# P_EV.net
KiCad netlist of a schematic drawn in Altium Designer
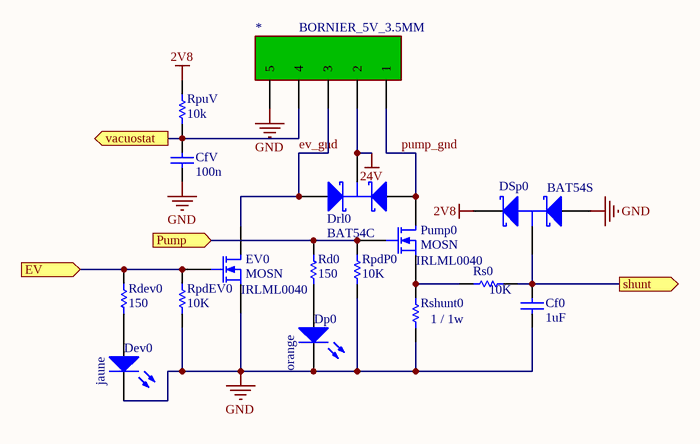
[diagram p0: P+EV.SchDoc]

(export (version "E")
  (design (tool "Eeschema 10.0.6"))
  (components
    (comp (ref "*")
      (value "BORNIER_5V_3.5MM")
      (footprint "BORNIER_5V_3.5MM_femelle_90")
      (libsource (lib "Connecteur") (part "BORNIER_5V_3.5MM"))
    )
    (comp (ref "Cf0")
      (value "1uF")
      (footprint "C0805_N")
      (description "Capacitor")
      (fields (field (name "PUBLISHER") "Altium Limited"))
      (libsource (lib "_ROBOT") (part "Condensateur"))
    )
    (comp (ref "CfV")
      (value "100n")
      (footprint "C0805_N")
      (description "Capacitor")
      (fields (field (name "PUBLISHER") "Altium Limited"))
      (libsource (lib "_ROBOT") (part "Condensateur"))
    )
    (comp (ref "Dev0")
      (value "jaune")
      (footprint "LED_0805")
      (description "Typical LED")
      (fields (field (name "PUBLISHER") "Altium Limited"))
      (libsource (lib "_ROBOT") (part "LED"))
    )
    (comp (ref "Dp0")
      (value "orange")
      (footprint "LED_0805")
      (description "Typical LED")
      (fields (field (name "PUBLISHER") "Altium Limited"))
      (libsource (lib "_ROBOT") (part "LED"))
    )
    (comp (ref "Drl0")
      (value "BAT54C")
      (footprint "SOT23-3N")
      (description "DIODE SCHOTTKY DOUBLE")
      (fields (field (name "MANUFACTURER") "ZETEX"))
      (libsource (lib "_ROBOT") (part "Diode Shottky double BAT54C"))
    )
    (comp (ref "DSp0")
      (value "BAT54S")
      (footprint "SOT23-3N")
      (description "DIODE SCHOTTKY DOUBLE")
      (fields (field (name "MANUFACTURER") "ZETEX"))
      (libsource (lib "_ROBOT") (part "Diode Shottky double BAT54S"))
    )
    (comp (ref "EV0")
      (value "MOSN")
      (footprint "SOT23-3N")
      (description "N-Channel MOSFET")
      (fields (field (name "ALTIUM_UNNAMED_1") "IRLML0040") (field (name "PUBLISHER") "Altium Limited"))
      (libsource (lib "_ROBOT") (part "Transistor MOSFET-N"))
    )
    (comp (ref "Pump0")
      (value "MOSN")
      (footprint "SOT23-3N")
      (description "N-Channel MOSFET")
      (fields (field (name "ALTIUM_UNNAMED_1") "IRLML0040") (field (name "PUBLISHER") "Altium Limited"))
      (libsource (lib "_ROBOT") (part "Transistor MOSFET-N"))
    )
    (comp (ref "Rd0")
      (value "150")
      (footprint "R1206_N")
      (description "Resistor")
      (fields (field (name "PUBLISHER") "Altium Limited"))
      (libsource (lib "_ROBOT") (part "Resistor"))
    )
    (comp (ref "Rdev0")
      (value "150")
      (footprint "R1206_N")
      (description "Resistor")
      (fields (field (name "PUBLISHER") "Altium Limited"))
      (libsource (lib "_ROBOT") (part "Resistor"))
    )
    (comp (ref "RpdEV0")
      (value "10K")
      (footprint "R1206_N")
      (description "Resistor")
      (fields (field (name "PUBLISHER") "Altium Limited"))
      (libsource (lib "_ROBOT") (part "Resistor"))
    )
    (comp (ref "RpdP0")
      (value "10K")
      (footprint "R1206_N")
      (description "Resistor")
      (fields (field (name "PUBLISHER") "Altium Limited"))
      (libsource (lib "_ROBOT") (part "Resistor"))
    )
    (comp (ref "RpuV")
      (value "10k")
      (footprint "R1206_N")
      (description "Resistor")
      (fields (field (name "PUBLISHER") "Altium Limited"))
      (libsource (lib "_ROBOT") (part "Resistor"))
    )
    (comp (ref "Rs0")
      (value "10K")
      (footprint "R1206_N")
      (description "Resistor")
      (fields (field (name "PUBLISHER") "Altium Limited"))
      (libsource (lib "_ROBOT") (part "Resistor"))
    )
    (comp (ref "Rshunt0")
      (value "1 / 1w")
      (footprint "INDUCTANCE_CMS_1812")
      (description "Resistor")
      (fields (field (name "PUBLISHER") "Altium Limited"))
      (libsource (lib "_ROBOT") (part "Resistor"))
    )
  )
  (nets
    (net (code "1") (name "/EV") (class "Default")
      (node (ref "EV0") (pin "1") (pinfunction "G_1") (pintype "passive"))
      (node (ref "Rdev0") (pin "2") (pinfunction "2_2") (pintype "passive"))
      (node (ref "RpdEV0") (pin "2") (pinfunction "2_2") (pintype "passive"))
    )
    (net (code "2") (name "/Pump") (class "Default")
      (node (ref "Pump0") (pin "1") (pinfunction "G_1") (pintype "passive"))
      (node (ref "Rd0") (pin "2") (pinfunction "2_2") (pintype "passive"))
      (node (ref "RpdP0") (pin "2") (pinfunction "2_2") (pintype "passive"))
    )
    (net (code "3") (name "/ev_gnd") (class "Default")
      (node (ref "*") (pin "3") (pinfunction "3_3") (pintype "passive"))
      (node (ref "Drl0") (pin "1") (pinfunction "A1_1") (pintype "passive"))
      (node (ref "EV0") (pin "3") (pinfunction "D_3") (pintype "passive"))
    )
    (net (code "4") (name "/pump_gnd") (class "Default")
      (node (ref "*") (pin "1") (pinfunction "1_1") (pintype "passive"))
      (node (ref "Drl0") (pin "2") (pinfunction "A2_2") (pintype "passive"))
      (node (ref "Pump0") (pin "3") (pinfunction "D_3") (pintype "passive"))
    )
    (net (code "5") (name "/shunt") (class "Default")
      (node (ref "Cf0") (pin "2") (pinfunction "2_2") (pintype "passive"))
      (node (ref "DSp0") (pin "3") (pinfunction "C_3") (pintype "passive"))
      (node (ref "Rs0") (pin "2") (pinfunction "2_2") (pintype "passive"))
    )
    (net (code "6") (name "/vacuostat") (class "Default")
      (node (ref "*") (pin "4") (pinfunction "4_4") (pintype "passive"))
      (node (ref "CfV") (pin "2") (pinfunction "2_2") (pintype "passive"))
      (node (ref "RpuV") (pin "1") (pinfunction "1_1") (pintype "passive"))
    )
    (net (code "7") (name "2V8") (class "Default")
      (node (ref "DSp0") (pin "2") (pinfunction "K_2") (pintype "passive"))
      (node (ref "RpuV") (pin "2") (pinfunction "2_2") (pintype "passive"))
    )
    (net (code "8") (name "24V") (class "Default")
      (node (ref "*") (pin "2") (pinfunction "2_2") (pintype "passive"))
      (node (ref "Drl0") (pin "3") (pinfunction "K_3") (pintype "passive"))
    )
    (net (code "9") (name "GND") (class "Default")
      (node (ref "*") (pin "5") (pinfunction "5_5") (pintype "passive"))
      (node (ref "Cf0") (pin "1") (pinfunction "1_1") (pintype "passive"))
      (node (ref "CfV") (pin "1") (pinfunction "1_1") (pintype "passive"))
      (node (ref "DSp0") (pin "1") (pinfunction "A_1") (pintype "passive"))
      (node (ref "Dev0") (pin "2") (pinfunction "K_2") (pintype "passive"))
      (node (ref "Dp0") (pin "2") (pinfunction "K_2") (pintype "passive"))
      (node (ref "EV0") (pin "2") (pinfunction "S_2") (pintype "passive"))
      (node (ref "RpdEV0") (pin "1") (pinfunction "1_1") (pintype "passive"))
      (node (ref "RpdP0") (pin "1") (pinfunction "1_1") (pintype "passive"))
      (node (ref "Rshunt0") (pin "1") (pinfunction "1_1") (pintype "passive"))
    )
    (net (code "10") (name "Net-(Dev0-A)") (class "Default")
      (node (ref "Dev0") (pin "1") (pinfunction "A_1") (pintype "passive"))
      (node (ref "Rdev0") (pin "1") (pinfunction "1_1") (pintype "passive"))
    )
    (net (code "11") (name "Net-(Dp0-A)") (class "Default")
      (node (ref "Dp0") (pin "1") (pinfunction "A_1") (pintype "passive"))
      (node (ref "Rd0") (pin "1") (pinfunction "1_1") (pintype "passive"))
    )
    (net (code "12") (name "Net-(Pump0-S)") (class "Default")
      (node (ref "Pump0") (pin "2") (pinfunction "S_2") (pintype "passive"))
      (node (ref "Rs0") (pin "1") (pinfunction "1_1") (pintype "passive"))
      (node (ref "Rshunt0") (pin "2") (pinfunction "2_2") (pintype "passive"))
    )
  )
)
